# dm_out.net
KiCad netlist of a schematic drawn in EAGLE
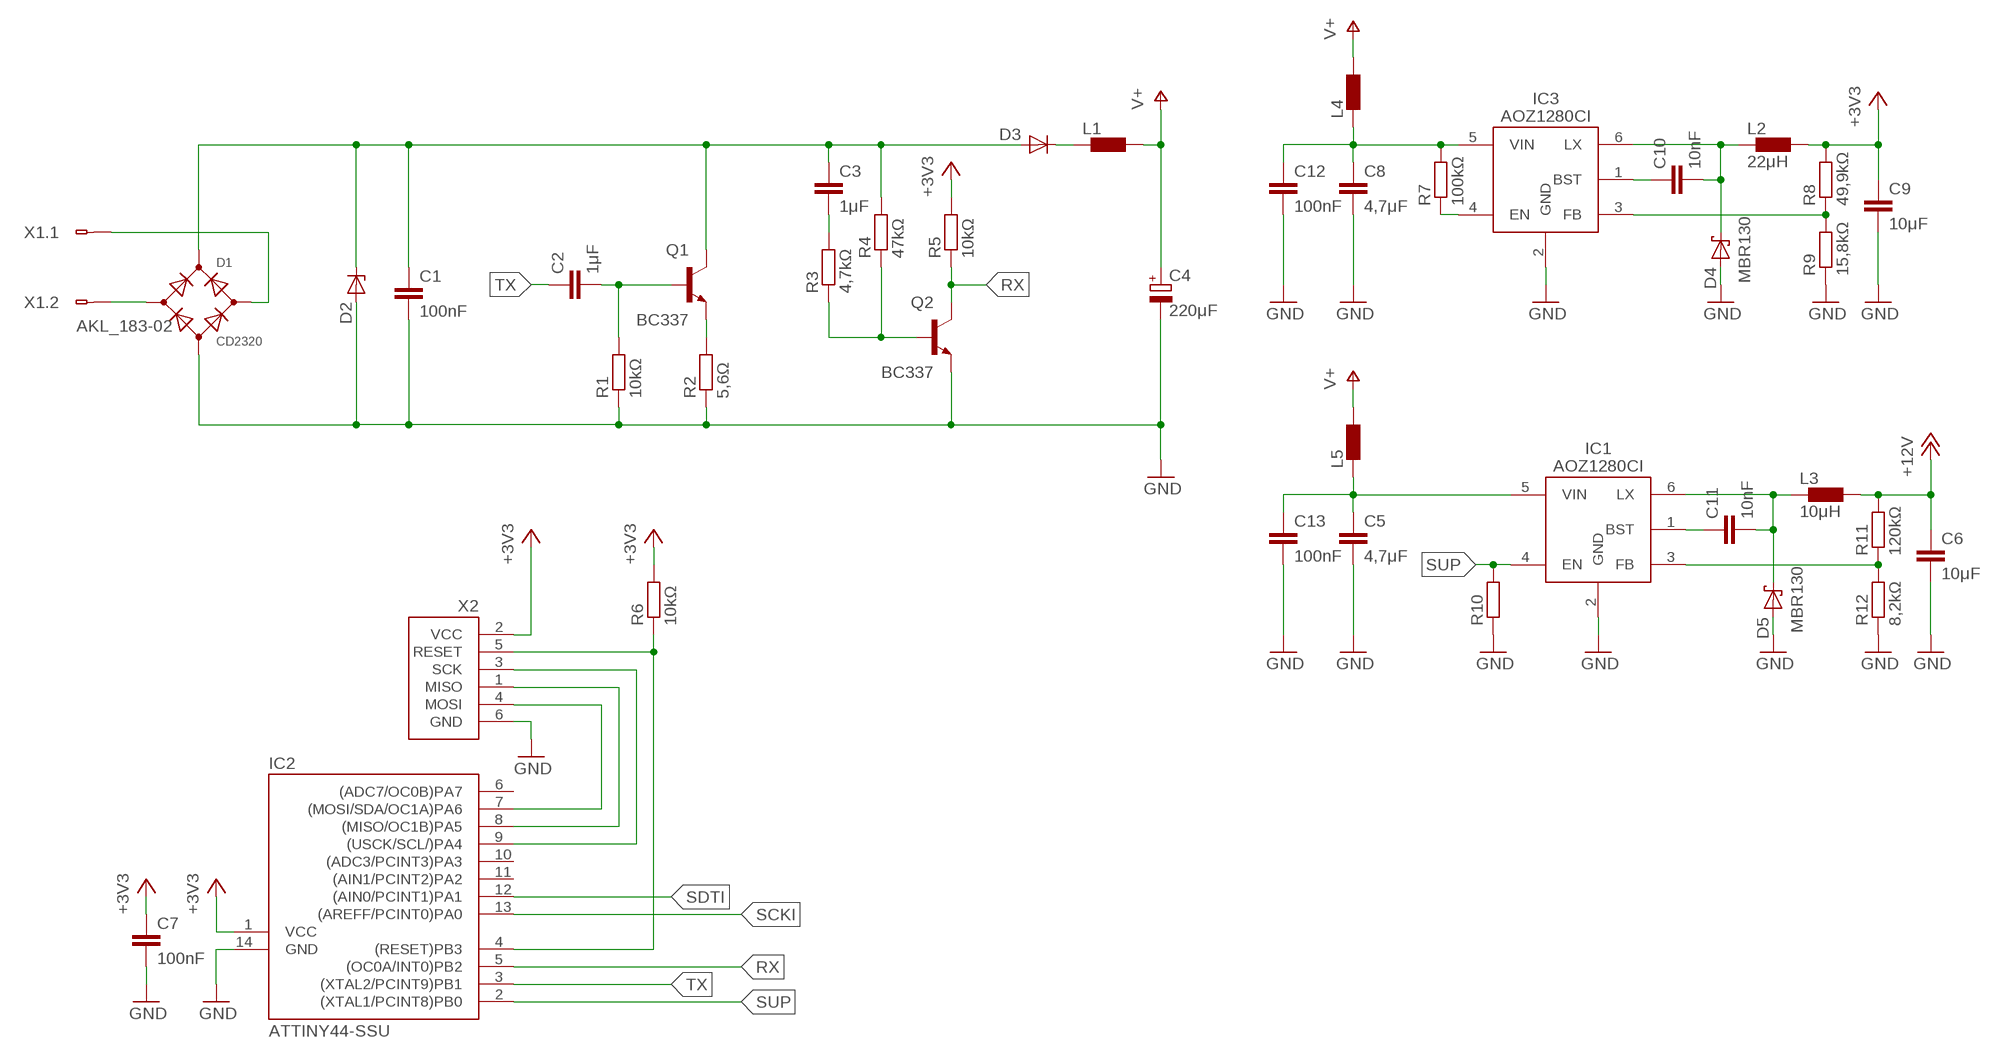
[diagram p0: schematic, sheet 1]

(export (version "E")
  (design (tool "Eeschema 10.0.6"))
  (components
    (comp (ref "C1")
      (value "100nF")
      (footprint "eagle-import:CHIP_1206")
      (libsource (lib "eagle-import") (part "C_1206"))
    )
    (comp (ref "C2")
      (value "1μF")
      (footprint "eagle-import:CHIP_1206")
      (libsource (lib "eagle-import") (part "C_1206"))
    )
    (comp (ref "C3")
      (value "1μF")
      (footprint "eagle-import:CHIP_1206")
      (libsource (lib "eagle-import") (part "C_1206"))
    )
    (comp (ref "C4")
      (value "220μF")
      (footprint "eagle-import:E5-13")
      (libsource (lib "eagle-import") (part "C_EL_E5-13"))
    )
    (comp (ref "C5")
      (value "4,7μF")
      (footprint "eagle-import:CHIP_1206")
      (libsource (lib "eagle-import") (part "C_1206"))
    )
    (comp (ref "C6")
      (value "10μF")
      (footprint "eagle-import:CHIP_1206")
      (libsource (lib "eagle-import") (part "C_1206"))
    )
    (comp (ref "C7")
      (value "100nF")
      (footprint "eagle-import:CHIP_0603")
      (libsource (lib "eagle-import") (part "C_0603"))
    )
    (comp (ref "C8")
      (value "4,7μF")
      (footprint "eagle-import:CHIP_1206")
      (libsource (lib "eagle-import") (part "C_1206"))
    )
    (comp (ref "C9")
      (value "10μF")
      (footprint "eagle-import:CHIP_1206")
      (libsource (lib "eagle-import") (part "C_1206"))
    )
    (comp (ref "C10")
      (value "10nF")
      (footprint "eagle-import:CHIP_0603")
      (libsource (lib "eagle-import") (part "C_0603"))
    )
    (comp (ref "C11")
      (value "10nF")
      (footprint "eagle-import:CHIP_0603")
      (libsource (lib "eagle-import") (part "C_0603"))
    )
    (comp (ref "C12")
      (value "100nF")
      (footprint "eagle-import:CHIP_0805")
      (libsource (lib "eagle-import") (part "C_0805"))
    )
    (comp (ref "C13")
      (value "100nF")
      (footprint "eagle-import:CHIP_0805")
      (libsource (lib "eagle-import") (part "C_0805"))
    )
    (comp (ref "D1")
      (value "CD2320")
      (footprint "eagle-import:2320")
      (libsource (lib "eagle-import") (part "CD2320"))
    )
    (comp (ref "D2")
      (value "Z-DIODE-SOD123")
      (footprint "eagle-import:SOD123")
      (libsource (lib "eagle-import") (part "Z-DIODE-SOD123"))
    )
    (comp (ref "D3")
      (value "DIODE-SOD123")
      (footprint "eagle-import:SOD123")
      (libsource (lib "eagle-import") (part "DIODE-SOD123"))
    )
    (comp (ref "D4")
      (value "MBR130")
      (footprint "eagle-import:SOD123")
      (libsource (lib "eagle-import") (part "SHOTKY-DIODE-SOD123"))
    )
    (comp (ref "D5")
      (value "MBR130")
      (footprint "eagle-import:SOD123")
      (libsource (lib "eagle-import") (part "SHOTKY-DIODE-SOD123"))
    )
    (comp (ref "IC1")
      (value "AOZ1280CI")
      (footprint "eagle-import:SOT23-6_095")
      (libsource (lib "eagle-import") (part "AOZ1280CI"))
    )
    (comp (ref "IC2")
      (value "ATTINY44-SSU")
      (footprint "eagle-import:SOP14_127")
      (libsource (lib "eagle-import") (part "ATTINY44-SSU"))
    )
    (comp (ref "IC3")
      (value "AOZ1280CI")
      (footprint "eagle-import:SOT23-6_095")
      (libsource (lib "eagle-import") (part "AOZ1280CI"))
    )
    (comp (ref "L1")
      (value "L_0805")
      (footprint "eagle-import:CHIP_0805")
      (libsource (lib "eagle-import") (part "L_0805"))
    )
    (comp (ref "L2")
      (value "22μH")
      (footprint "eagle-import:CHIP_0805")
      (libsource (lib "eagle-import") (part "L_0805"))
    )
    (comp (ref "L3")
      (value "10μH")
      (footprint "eagle-import:CHIP_1210")
      (libsource (lib "eagle-import") (part "L_1210"))
    )
    (comp (ref "L4")
      (value "L_0805")
      (footprint "eagle-import:CHIP_0805")
      (libsource (lib "eagle-import") (part "L_0805"))
    )
    (comp (ref "L5")
      (value "L_0805")
      (footprint "eagle-import:CHIP_0805")
      (libsource (lib "eagle-import") (part "L_0805"))
    )
    (comp (ref "Q1")
      (value "BC337")
      (footprint "eagle-import:SOT23")
      (libsource (lib "eagle-import") (part "NPN-SOT23-BEC"))
    )
    (comp (ref "Q2")
      (value "BC337")
      (footprint "eagle-import:SOT23")
      (libsource (lib "eagle-import") (part "NPN-SOT23-BEC"))
    )
    (comp (ref "R1")
      (value "10kΩ")
      (footprint "eagle-import:CHIP_0603")
      (libsource (lib "eagle-import") (part "R_0603"))
    )
    (comp (ref "R2")
      (value "5,6Ω")
      (footprint "eagle-import:CHIP_1206")
      (libsource (lib "eagle-import") (part "R_1206"))
    )
    (comp (ref "R3")
      (value "4,7kΩ")
      (footprint "eagle-import:CHIP_0603")
      (libsource (lib "eagle-import") (part "R_0603"))
    )
    (comp (ref "R4")
      (value "47kΩ")
      (footprint "eagle-import:CHIP_0603")
      (libsource (lib "eagle-import") (part "R_0603"))
    )
    (comp (ref "R5")
      (value "10kΩ")
      (footprint "eagle-import:CHIP_0603")
      (libsource (lib "eagle-import") (part "R_0603"))
    )
    (comp (ref "R6")
      (value "10kΩ")
      (footprint "eagle-import:CHIP_0603")
      (libsource (lib "eagle-import") (part "R_0603"))
    )
    (comp (ref "R7")
      (value "100kΩ")
      (footprint "eagle-import:CHIP_0603")
      (libsource (lib "eagle-import") (part "R_0603"))
    )
    (comp (ref "R8")
      (value "49,9kΩ")
      (footprint "eagle-import:CHIP_0603")
      (libsource (lib "eagle-import") (part "R_0603"))
    )
    (comp (ref "R9")
      (value "15,8kΩ")
      (footprint "eagle-import:CHIP_0603")
      (libsource (lib "eagle-import") (part "R_0603"))
    )
    (comp (ref "R10")
      (value "R_0603")
      (footprint "eagle-import:CHIP_0603")
      (libsource (lib "eagle-import") (part "R_0603"))
    )
    (comp (ref "R11")
      (value "120kΩ")
      (footprint "eagle-import:CHIP_0603")
      (libsource (lib "eagle-import") (part "R_0603"))
    )
    (comp (ref "R12")
      (value "8,2kΩ")
      (footprint "eagle-import:CHIP_0603")
      (libsource (lib "eagle-import") (part "R_0603"))
    )
    (comp (ref "X1")
      (value "AKL_183-02")
      (footprint "eagle-import:AKL_183-02")
      (libsource (lib "eagle-import") (part "AKL_183-02"))
    )
    (comp (ref "X2")
      (value "ISP-AVR6")
      (footprint "eagle-import:ML6")
      (libsource (lib "eagle-import") (part "ISP-AVR6"))
    )
  )
  (nets
    (net (code "1") (name "+3V3") (class "Default")
      (node (ref "C7") (pin "1") (pinfunction "1_1") (pintype "passive"))
      (node (ref "C9") (pin "1") (pinfunction "1_1") (pintype "passive"))
      (node (ref "IC2") (pin "1") (pinfunction "VCC_1") (pintype "power_in"))
      (node (ref "L2") (pin "1") (pinfunction "1_1") (pintype "passive"))
      (node (ref "R5") (pin "2") (pinfunction "2_2") (pintype "passive"))
      (node (ref "R6") (pin "2") (pinfunction "2_2") (pintype "passive"))
      (node (ref "R8") (pin "2") (pinfunction "2_2") (pintype "passive"))
      (node (ref "X2") (pin "2") (pinfunction "VCC_2") (pintype "power_in"))
    )
    (net (code "2") (name "+12V") (class "Default")
      (node (ref "C6") (pin "1") (pinfunction "1_1") (pintype "passive"))
      (node (ref "L3") (pin "1") (pinfunction "1_1") (pintype "passive"))
      (node (ref "R11") (pin "2") (pinfunction "2_2") (pintype "passive"))
    )
    (net (code "3") (name "GND") (class "Default")
      (node (ref "C1") (pin "2") (pinfunction "2_2") (pintype "passive"))
      (node (ref "C12") (pin "2") (pinfunction "2_2") (pintype "passive"))
      (node (ref "C13") (pin "2") (pinfunction "2_2") (pintype "passive"))
      (node (ref "C4") (pin "-") (pinfunction "-_-") (pintype "passive"))
      (node (ref "C5") (pin "2") (pinfunction "2_2") (pintype "passive"))
      (node (ref "C6") (pin "2") (pinfunction "2_2") (pintype "passive"))
      (node (ref "C7") (pin "2") (pinfunction "2_2") (pintype "passive"))
      (node (ref "C8") (pin "2") (pinfunction "2_2") (pintype "passive"))
      (node (ref "C9") (pin "2") (pinfunction "2_2") (pintype "passive"))
      (node (ref "D1") (pin "-") (pinfunction "-_-") (pintype "passive"))
      (node (ref "D2") (pin "A") (pinfunction "A_A") (pintype "passive"))
      (node (ref "D4") (pin "A") (pinfunction "A_A") (pintype "passive"))
      (node (ref "D5") (pin "A") (pinfunction "A_A") (pintype "passive"))
      (node (ref "IC1") (pin "2") (pinfunction "GND_2") (pintype "power_in"))
      (node (ref "IC2") (pin "14") (pinfunction "GND_14") (pintype "power_in"))
      (node (ref "IC3") (pin "2") (pinfunction "GND_2") (pintype "power_in"))
      (node (ref "Q2") (pin "2") (pinfunction "E_2") (pintype "passive"))
      (node (ref "R1") (pin "1") (pinfunction "1_1") (pintype "passive"))
      (node (ref "R10") (pin "1") (pinfunction "1_1") (pintype "passive"))
      (node (ref "R12") (pin "1") (pinfunction "1_1") (pintype "passive"))
      (node (ref "R2") (pin "1") (pinfunction "1_1") (pintype "passive"))
      (node (ref "R9") (pin "1") (pinfunction "1_1") (pintype "passive"))
      (node (ref "X2") (pin "6") (pinfunction "GND_6") (pintype "power_in"))
    )
    (net (code "4") (name "Net-(C3-Pad2)") (class "Default")
      (node (ref "C3") (pin "2") (pinfunction "2_2") (pintype "passive"))
      (node (ref "R3") (pin "2") (pinfunction "2_2") (pintype "passive"))
    )
    (net (code "5") (name "Net-(D3-PadK)") (class "Default")
      (node (ref "D3") (pin "K") (pinfunction "K_K") (pintype "passive"))
      (node (ref "L1") (pin "2") (pinfunction "2_2") (pintype "passive"))
    )
    (net (code "6") (name "Net-(IC1-BST)") (class "Default")
      (node (ref "C11") (pin "1") (pinfunction "1_1") (pintype "passive"))
      (node (ref "IC1") (pin "1") (pinfunction "BST_1") (pintype "bidirectional"))
    )
    (net (code "7") (name "Net-(IC1-FB)") (class "Default")
      (node (ref "IC1") (pin "3") (pinfunction "FB_3") (pintype "input"))
      (node (ref "R11") (pin "1") (pinfunction "1_1") (pintype "passive"))
      (node (ref "R12") (pin "2") (pinfunction "2_2") (pintype "passive"))
    )
    (net (code "8") (name "Net-(IC1-LX)") (class "Default")
      (node (ref "C11") (pin "2") (pinfunction "2_2") (pintype "passive"))
      (node (ref "D5") (pin "K") (pinfunction "K_K") (pintype "passive"))
      (node (ref "IC1") (pin "6") (pinfunction "LX_6") (pintype "output"))
      (node (ref "L3") (pin "2") (pinfunction "2_2") (pintype "passive"))
    )
    (net (code "9") (name "Net-(IC1-VIN)") (class "Default")
      (node (ref "C13") (pin "1") (pinfunction "1_1") (pintype "passive"))
      (node (ref "C5") (pin "1") (pinfunction "1_1") (pintype "passive"))
      (node (ref "IC1") (pin "5") (pinfunction "VIN_5") (pintype "power_in"))
      (node (ref "L5") (pin "2") (pinfunction "2_2") (pintype "passive"))
    )
    (net (code "10") (name "Net-(IC2-(MISO{slash}OC1B)PA5)") (class "Default")
      (node (ref "IC2") (pin "8") (pinfunction "(MISO/OC1B)PA5_8") (pintype "bidirectional"))
      (node (ref "X2") (pin "1") (pinfunction "MISO_1") (pintype "passive"))
    )
    (net (code "11") (name "Net-(IC2-(MOSI{slash}SDA{slash}OC1A)PA6)") (class "Default")
      (node (ref "IC2") (pin "7") (pinfunction "(MOSI/SDA/OC1A)PA6_7") (pintype "bidirectional"))
      (node (ref "X2") (pin "4") (pinfunction "MOSI_4") (pintype "passive"))
    )
    (net (code "12") (name "Net-(IC2-(RESET)PB3)") (class "Default")
      (node (ref "IC2") (pin "4") (pinfunction "(RESET)PB3_4") (pintype "bidirectional"))
      (node (ref "R6") (pin "1") (pinfunction "1_1") (pintype "passive"))
      (node (ref "X2") (pin "5") (pinfunction "RESET_5") (pintype "passive"))
    )
    (net (code "13") (name "Net-(IC2-(USCK{slash}SCL{slash})PA4)") (class "Default")
      (node (ref "IC2") (pin "9") (pinfunction "(USCK/SCL/)PA4_9") (pintype "bidirectional"))
      (node (ref "X2") (pin "3") (pinfunction "SCK_3") (pintype "passive"))
    )
    (net (code "14") (name "Net-(IC3-BST)") (class "Default")
      (node (ref "C10") (pin "1") (pinfunction "1_1") (pintype "passive"))
      (node (ref "IC3") (pin "1") (pinfunction "BST_1") (pintype "bidirectional"))
    )
    (net (code "15") (name "Net-(IC3-EN)") (class "Default")
      (node (ref "IC3") (pin "4") (pinfunction "EN_4") (pintype "input"))
      (node (ref "R7") (pin "1") (pinfunction "1_1") (pintype "passive"))
    )
    (net (code "16") (name "Net-(IC3-FB)") (class "Default")
      (node (ref "IC3") (pin "3") (pinfunction "FB_3") (pintype "input"))
      (node (ref "R8") (pin "1") (pinfunction "1_1") (pintype "passive"))
      (node (ref "R9") (pin "2") (pinfunction "2_2") (pintype "passive"))
    )
    (net (code "17") (name "Net-(IC3-LX)") (class "Default")
      (node (ref "C10") (pin "2") (pinfunction "2_2") (pintype "passive"))
      (node (ref "D4") (pin "K") (pinfunction "K_K") (pintype "passive"))
      (node (ref "IC3") (pin "6") (pinfunction "LX_6") (pintype "output"))
      (node (ref "L2") (pin "2") (pinfunction "2_2") (pintype "passive"))
    )
    (net (code "18") (name "Net-(IC3-VIN)") (class "Default")
      (node (ref "C12") (pin "1") (pinfunction "1_1") (pintype "passive"))
      (node (ref "C8") (pin "1") (pinfunction "1_1") (pintype "passive"))
      (node (ref "IC3") (pin "5") (pinfunction "VIN_5") (pintype "power_in"))
      (node (ref "L4") (pin "2") (pinfunction "2_2") (pintype "passive"))
      (node (ref "R7") (pin "2") (pinfunction "2_2") (pintype "passive"))
    )
    (net (code "19") (name "Net-(Q1-B)") (class "Default")
      (node (ref "C2") (pin "2") (pinfunction "2_2") (pintype "passive"))
      (node (ref "Q1") (pin "1") (pinfunction "B_1") (pintype "passive"))
      (node (ref "R1") (pin "2") (pinfunction "2_2") (pintype "passive"))
    )
    (net (code "20") (name "Net-(Q1-C)") (class "Default")
      (node (ref "C1") (pin "1") (pinfunction "1_1") (pintype "passive"))
      (node (ref "C3") (pin "1") (pinfunction "1_1") (pintype "passive"))
      (node (ref "D1") (pin "+") (pinfunction "+_+") (pintype "passive"))
      (node (ref "D2") (pin "K") (pinfunction "K_K") (pintype "passive"))
      (node (ref "D3") (pin "A") (pinfunction "A_A") (pintype "passive"))
      (node (ref "Q1") (pin "3") (pinfunction "C_3") (pintype "passive"))
      (node (ref "R4") (pin "2") (pinfunction "2_2") (pintype "passive"))
    )
    (net (code "21") (name "Net-(Q1-E)") (class "Default")
      (node (ref "Q1") (pin "2") (pinfunction "E_2") (pintype "passive"))
      (node (ref "R2") (pin "2") (pinfunction "2_2") (pintype "passive"))
    )
    (net (code "22") (name "Net-(Q2-B)") (class "Default")
      (node (ref "Q2") (pin "1") (pinfunction "B_1") (pintype "passive"))
      (node (ref "R3") (pin "1") (pinfunction "1_1") (pintype "passive"))
      (node (ref "R4") (pin "1") (pinfunction "1_1") (pintype "passive"))
    )
    (net (code "23") (name "Net-(X1A-A)") (class "Default")
      (node (ref "D1") (pin "AC2") (pinfunction "AC2_AC2") (pintype "passive"))
      (node (ref "X1") (pin "1") (pinfunction "A_1") (pintype "passive"))
    )
    (net (code "24") (name "Net-(X1B-A)") (class "Default")
      (node (ref "D1") (pin "AC1") (pinfunction "AC1_AC1") (pintype "passive"))
      (node (ref "X1") (pin "2") (pinfunction "A_2") (pintype "passive"))
    )
    (net (code "25") (name "RX") (class "Default")
      (node (ref "IC2") (pin "5") (pinfunction "(OC0A/INT0)PB2_5") (pintype "bidirectional"))
      (node (ref "Q2") (pin "3") (pinfunction "C_3") (pintype "passive"))
      (node (ref "R5") (pin "1") (pinfunction "1_1") (pintype "passive"))
    )
    (net (code "26") (name "SCKI") (class "Default")
      (node (ref "IC2") (pin "13") (pinfunction "(AREFF/PCINT0)PA0_13") (pintype "bidirectional"))
    )
    (net (code "27") (name "SDTI") (class "Default")
      (node (ref "IC2") (pin "12") (pinfunction "(AIN0/PCINT1)PA1_12") (pintype "bidirectional"))
    )
    (net (code "28") (name "SUP") (class "Default")
      (node (ref "IC1") (pin "4") (pinfunction "EN_4") (pintype "input"))
      (node (ref "IC2") (pin "2") (pinfunction "(XTAL1/PCINT8)PB0_2") (pintype "bidirectional"))
      (node (ref "R10") (pin "2") (pinfunction "2_2") (pintype "passive"))
    )
    (net (code "29") (name "TX") (class "Default")
      (node (ref "C2") (pin "1") (pinfunction "1_1") (pintype "passive"))
      (node (ref "IC2") (pin "3") (pinfunction "(XTAL2/PCINT9)PB1_3") (pintype "bidirectional"))
    )
    (net (code "30") (name "V+") (class "Default")
      (node (ref "C4") (pin "+") (pinfunction "+_+") (pintype "passive"))
      (node (ref "L1") (pin "1") (pinfunction "1_1") (pintype "passive"))
      (node (ref "L4") (pin "1") (pinfunction "1_1") (pintype "passive"))
      (node (ref "L5") (pin "1") (pinfunction "1_1") (pintype "passive"))
    )
    (net (code "31") (name "unconnected-(IC2-(ADC3{slash}PCINT3)PA3-Pad10)") (class "Default")
      (node (ref "IC2") (pin "10") (pinfunction "(ADC3/PCINT3)PA3_10") (pintype "bidirectional"))
    )
    (net (code "32") (name "unconnected-(IC2-(ADC7{slash}OC0B)PA7-Pad6)") (class "Default")
      (node (ref "IC2") (pin "6") (pinfunction "(ADC7/OC0B)PA7_6") (pintype "bidirectional"))
    )
    (net (code "33") (name "unconnected-(IC2-(AIN1{slash}PCINT2)PA2-Pad11)") (class "Default")
      (node (ref "IC2") (pin "11") (pinfunction "(AIN1/PCINT2)PA2_11") (pintype "bidirectional"))
    )
  )
)
